# 2_BUCK_schdoc.net
KiCad netlist of a schematic drawn in Altium Designer
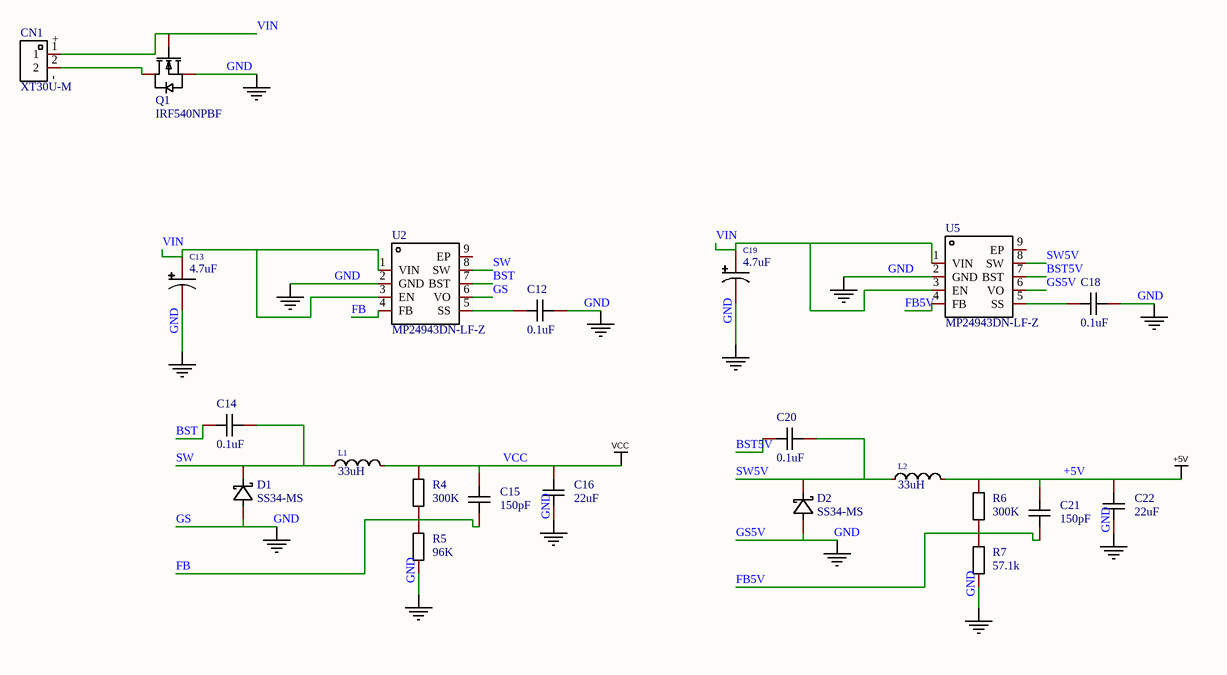
[diagram p0: 2_BUCK.schdoc.schdoc]

(export (version "E")
  (design (tool "Eeschema 10.0.6"))
  (components
    (comp (ref "C12")
      (value "0.1uF")
      (fields (field (name "NAME") "0.1uF"))
      (libsource (lib "altium-import") (part "root_0_CAP_0603_"))
    )
    (comp (ref "C13")
      (value "4.7uF")
      (description "容值:220uF;精度:±20%;额定电压:50V;纹波电流:220mA@120Hz;等效串联电阻:-;")
      (fields
        (field (name "NAME") "4.7uF")
        (field (name "MANUFACTURER") "Nichicon(尼吉康)")
        (field (name "MANUFACTURER PART") "UWT1H221MNL1GS")
      )
      (libsource (lib "altium-import") (part "root_0_UWT1H221MNL1GS_"))
    )
    (comp (ref "C14")
      (value "0.1uF")
      (fields (field (name "NAME") "0.1uF"))
      (libsource (lib "altium-import") (part "root_0_CAP_0603_"))
    )
    (comp (ref "C15")
      (value "150pF")
      (fields (field (name "NAME") "150pF"))
      (libsource (lib "altium-import") (part "root_3_CAP_0603_"))
    )
    (comp (ref "C16")
      (value "22uF")
      (fields (field (name "NAME") "22uF"))
      (libsource (lib "altium-import") (part "root_3_CAP_0603_"))
    )
    (comp (ref "C18")
      (value "0.1uF")
      (fields (field (name "NAME") "0.1uF"))
      (libsource (lib "altium-import") (part "root_0_CAP_0603_"))
    )
    (comp (ref "C19")
      (value "4.7uF")
      (description "容值:220uF;精度:±20%;额定电压:50V;纹波电流:220mA@120Hz;等效串联电阻:-;")
      (fields
        (field (name "NAME") "4.7uF")
        (field (name "MANUFACTURER") "Nichicon(尼吉康)")
        (field (name "MANUFACTURER PART") "UWT1H221MNL1GS")
      )
      (libsource (lib "altium-import") (part "root_0_UWT1H221MNL1GS_"))
    )
    (comp (ref "C20")
      (value "0.1uF")
      (fields (field (name "NAME") "0.1uF"))
      (libsource (lib "altium-import") (part "root_0_CAP_0603_"))
    )
    (comp (ref "C21")
      (value "150pF")
      (fields (field (name "NAME") "150pF"))
      (libsource (lib "altium-import") (part "root_3_CAP_0603_"))
    )
    (comp (ref "C22")
      (value "22uF")
      (fields (field (name "NAME") "22uF"))
      (libsource (lib "altium-import") (part "root_3_CAP_0603_"))
    )
    (comp (ref "CN1")
      (value "XT30U-M")
      (description "模型插头轻量版锂电池插头")
      (fields (field (name "NAME") "XT30U-M") (field (name "MANUFACTURER") "AMASS(艾迈斯)"))
      (libsource (lib "altium-import") (part "root_0_mirrored_XT30U-M_"))
    )
    (comp (ref "D1")
      (value "SS34-MS")
      (description "二极管配置:-;正向压降(Vf):550mV@3A;直流反向耐压(Vr):40V;平均整流电流(Io):3A;")
      (fields (field (name "NAME") "SS34-MS") (field (name "MANUFACTURER") "MSKSEMI(美森科)"))
      (libsource (lib "altium-import") (part "root_3_SS34-MS_"))
    )
    (comp (ref "D2")
      (value "SS34-MS")
      (description "二极管配置:-;正向压降(Vf):550mV@3A;直流反向耐压(Vr):40V;平均整流电流(Io):3A;")
      (fields (field (name "NAME") "SS34-MS") (field (name "MANUFACTURER") "MSKSEMI(美森科)"))
      (libsource (lib "altium-import") (part "root_3_SS34-MS_"))
    )
    (comp (ref "L1")
      (value "33uH")
      (fields
        (field (name "NAME") "33uH")
        (field (name "MANUFACTURER") "Sunlord(顺络)")
        (field (name "MANUFACTURER PART") "SDFL1608S100KTF")
      )
      (libsource (lib "altium-import") (part "root_0_L_0603_"))
    )
    (comp (ref "L2")
      (value "33uH")
      (fields
        (field (name "NAME") "33uH")
        (field (name "MANUFACTURER") "Sunlord(顺络)")
        (field (name "MANUFACTURER PART") "SDFL1608S100KTF")
      )
      (libsource (lib "altium-import") (part "root_0_L_0603_"))
    )
    (comp (ref "Q1")
      (value "IRF540NPBF")
      (description "类型:N沟道;漏源电压(Vdss):100V;连续漏极电流(Id):33A;功率(Pd):130W;导通电阻(RDS(on)@Vgs,Id):44mΩ@10V,16A;")
      (fields (field (name "NAME") "IRF540NPBF") (field (name "MANUFACTURER") "Infineon(英飞凌)"))
      (libsource (lib "altium-import") (part "root_3_mirrored_IRF540NPBF_"))
    )
    (comp (ref "R4")
      (value "300K")
      (fields (field (name "NAME") "300K"))
      (libsource (lib "altium-import") (part "root_3_Res_0603_"))
    )
    (comp (ref "R5")
      (value "96K")
      (fields (field (name "NAME") "96K"))
      (libsource (lib "altium-import") (part "root_3_Res_0603_"))
    )
    (comp (ref "R6")
      (value "300K")
      (fields (field (name "NAME") "300K"))
      (libsource (lib "altium-import") (part "root_3_Res_0603_"))
    )
    (comp (ref "R7")
      (value "57.1k")
      (fields (field (name "NAME") "57.1k"))
      (libsource (lib "altium-import") (part "root_3_Res_0603_"))
    )
    (comp (ref "U2")
      (value "MP24943DN-LF-Z")
      (description "最大输入电压:-;可输出电流:-;")
      (fields (field (name "NAME") "MP24943DN-LF-Z"))
      (libsource (lib "altium-import") (part "root_0_MP24943DN-LF-Z_"))
    )
    (comp (ref "U5")
      (value "MP24943DN-LF-Z")
      (description "最大输入电压:-;可输出电流:-;")
      (fields (field (name "NAME") "MP24943DN-LF-Z"))
      (libsource (lib "altium-import") (part "root_0_MP24943DN-LF-Z_"))
    )
  )
  (nets
    (net (code "1") (name "+5V") (class "Default")
      (node (ref "C21") (pin "1") (pinfunction "1_1") (pintype "passive"))
      (node (ref "C22") (pin "1") (pinfunction "1_1") (pintype "passive"))
      (node (ref "L2") (pin "2") (pinfunction "2_2") (pintype "passive"))
      (node (ref "R6") (pin "1") (pinfunction "1_1") (pintype "passive"))
    )
    (net (code "2") (name "/BST") (class "Default")
      (node (ref "C14") (pin "1") (pinfunction "1_1") (pintype "passive"))
      (node (ref "U2") (pin "7") (pinfunction "BST_7") (pintype "passive"))
    )
    (net (code "3") (name "/BST5V") (class "Default")
      (node (ref "C20") (pin "1") (pinfunction "1_1") (pintype "passive"))
      (node (ref "U5") (pin "7") (pinfunction "BST_7") (pintype "passive"))
    )
    (net (code "4") (name "/FB") (class "Default")
      (node (ref "C15") (pin "2") (pinfunction "2_2") (pintype "passive"))
      (node (ref "R4") (pin "2") (pinfunction "2_2") (pintype "passive"))
      (node (ref "R5") (pin "1") (pinfunction "1_1") (pintype "passive"))
      (node (ref "U2") (pin "4") (pinfunction "FB_4") (pintype "passive"))
    )
    (net (code "5") (name "/FB5V") (class "Default")
      (node (ref "C21") (pin "2") (pinfunction "2_2") (pintype "passive"))
      (node (ref "R6") (pin "2") (pinfunction "2_2") (pintype "passive"))
      (node (ref "R7") (pin "1") (pinfunction "1_1") (pintype "passive"))
      (node (ref "U5") (pin "4") (pinfunction "FB_4") (pintype "passive"))
    )
    (net (code "6") (name "/SW") (class "Default")
      (node (ref "C14") (pin "2") (pinfunction "2_2") (pintype "passive"))
      (node (ref "D1") (pin "1") (pinfunction "A_1") (pintype "passive"))
      (node (ref "L1") (pin "1") (pinfunction "1_1") (pintype "passive"))
      (node (ref "U2") (pin "8") (pinfunction "SW_8") (pintype "passive"))
    )
    (net (code "7") (name "/SW5V") (class "Default")
      (node (ref "C20") (pin "2") (pinfunction "2_2") (pintype "passive"))
      (node (ref "D2") (pin "1") (pinfunction "A_1") (pintype "passive"))
      (node (ref "L2") (pin "1") (pinfunction "1_1") (pintype "passive"))
      (node (ref "U5") (pin "8") (pinfunction "SW_8") (pintype "passive"))
    )
    (net (code "8") (name "/VIN") (class "Default")
      (node (ref "C13") (pin "1") (pinfunction "1_1") (pintype "passive"))
      (node (ref "C19") (pin "1") (pinfunction "1_1") (pintype "passive"))
      (node (ref "CN1") (pin "1") (pinfunction "1_1") (pintype "passive"))
      (node (ref "Q1") (pin "1") (pinfunction "G_1") (pintype "passive"))
      (node (ref "U2") (pin "1") (pinfunction "VIN_1") (pintype "passive"))
      (node (ref "U2") (pin "3") (pinfunction "EN_3") (pintype "passive"))
      (node (ref "U5") (pin "1") (pinfunction "VIN_1") (pintype "passive"))
      (node (ref "U5") (pin "3") (pinfunction "EN_3") (pintype "passive"))
    )
    (net (code "9") (name "<NO NET>") (class "Default")
      (node (ref "C12") (pin "2") (pinfunction "2_2") (pintype "passive"))
      (node (ref "C13") (pin "2") (pinfunction "2_2") (pintype "passive"))
      (node (ref "C16") (pin "2") (pinfunction "2_2") (pintype "passive"))
      (node (ref "C18") (pin "2") (pinfunction "2_2") (pintype "passive"))
      (node (ref "C19") (pin "2") (pinfunction "2_2") (pintype "passive"))
      (node (ref "C22") (pin "2") (pinfunction "2_2") (pintype "passive"))
      (node (ref "D1") (pin "2") (pinfunction "K_2") (pintype "passive"))
      (node (ref "D2") (pin "2") (pinfunction "K_2") (pintype "passive"))
      (node (ref "Q1") (pin "3") (pinfunction "S_3") (pintype "passive"))
      (node (ref "R5") (pin "2") (pinfunction "2_2") (pintype "passive"))
      (node (ref "R7") (pin "2") (pinfunction "2_2") (pintype "passive"))
      (node (ref "U2") (pin "2") (pinfunction "GND_2") (pintype "passive"))
      (node (ref "U2") (pin "6") (pinfunction "VO_6") (pintype "passive"))
      (node (ref "U5") (pin "2") (pinfunction "GND_2") (pintype "passive"))
      (node (ref "U5") (pin "6") (pinfunction "VO_6") (pintype "passive"))
    )
    (net (code "10") (name "Net-(Q1-D)") (class "Default")
      (node (ref "CN1") (pin "2") (pinfunction "2_2") (pintype "passive"))
      (node (ref "Q1") (pin "2") (pinfunction "D_2") (pintype "passive"))
    )
    (net (code "11") (name "Net-(U2-SS)") (class "Default")
      (node (ref "C12") (pin "1") (pinfunction "1_1") (pintype "passive"))
      (node (ref "U2") (pin "5") (pinfunction "SS_5") (pintype "passive"))
    )
    (net (code "12") (name "Net-(U5-SS)") (class "Default")
      (node (ref "C18") (pin "1") (pinfunction "1_1") (pintype "passive"))
      (node (ref "U5") (pin "5") (pinfunction "SS_5") (pintype "passive"))
    )
    (net (code "13") (name "VCC") (class "Default")
      (node (ref "C15") (pin "1") (pinfunction "1_1") (pintype "passive"))
      (node (ref "C16") (pin "1") (pinfunction "1_1") (pintype "passive"))
      (node (ref "L1") (pin "2") (pinfunction "2_2") (pintype "passive"))
      (node (ref "R4") (pin "1") (pinfunction "1_1") (pintype "passive"))
    )
    (net (code "14") (name "unconnected-(U2-EP-Pad9)") (class "Default")
      (node (ref "U2") (pin "9") (pinfunction "EP_9") (pintype "passive"))
    )
    (net (code "15") (name "unconnected-(U5-EP-Pad9)") (class "Default")
      (node (ref "U5") (pin "9") (pinfunction "EP_9") (pintype "passive"))
    )
  )
)
